# 1_Power.net
KiCad netlist of a schematic drawn in Altium Designer
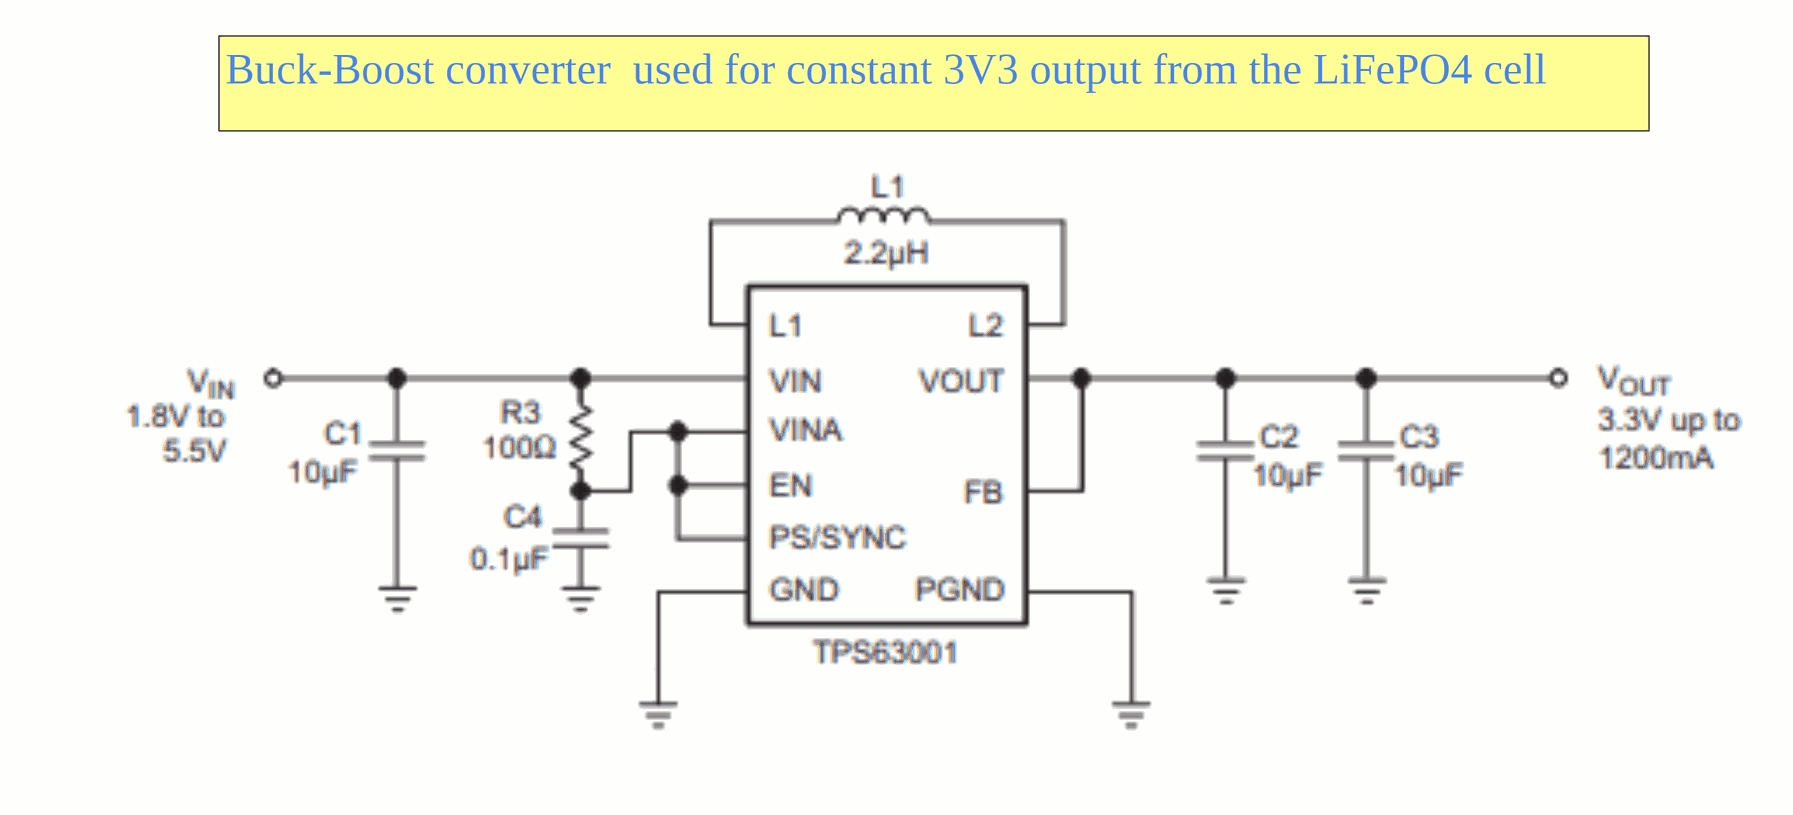
[diagram p0: 1_Power.SchDoc, top left]
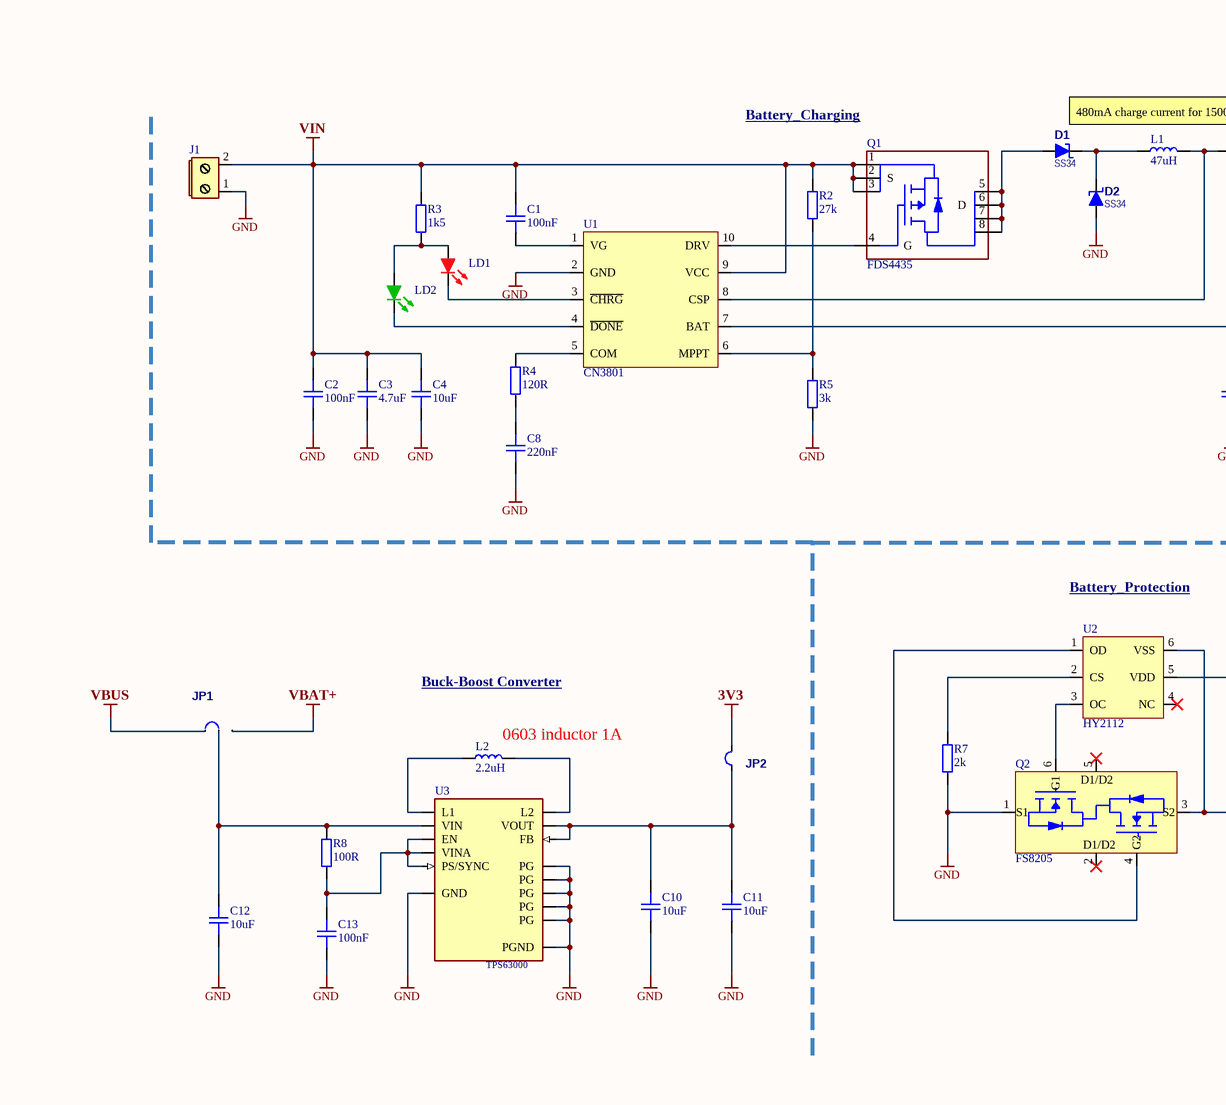
[diagram p1: 1_Power.SchDoc, top middle]
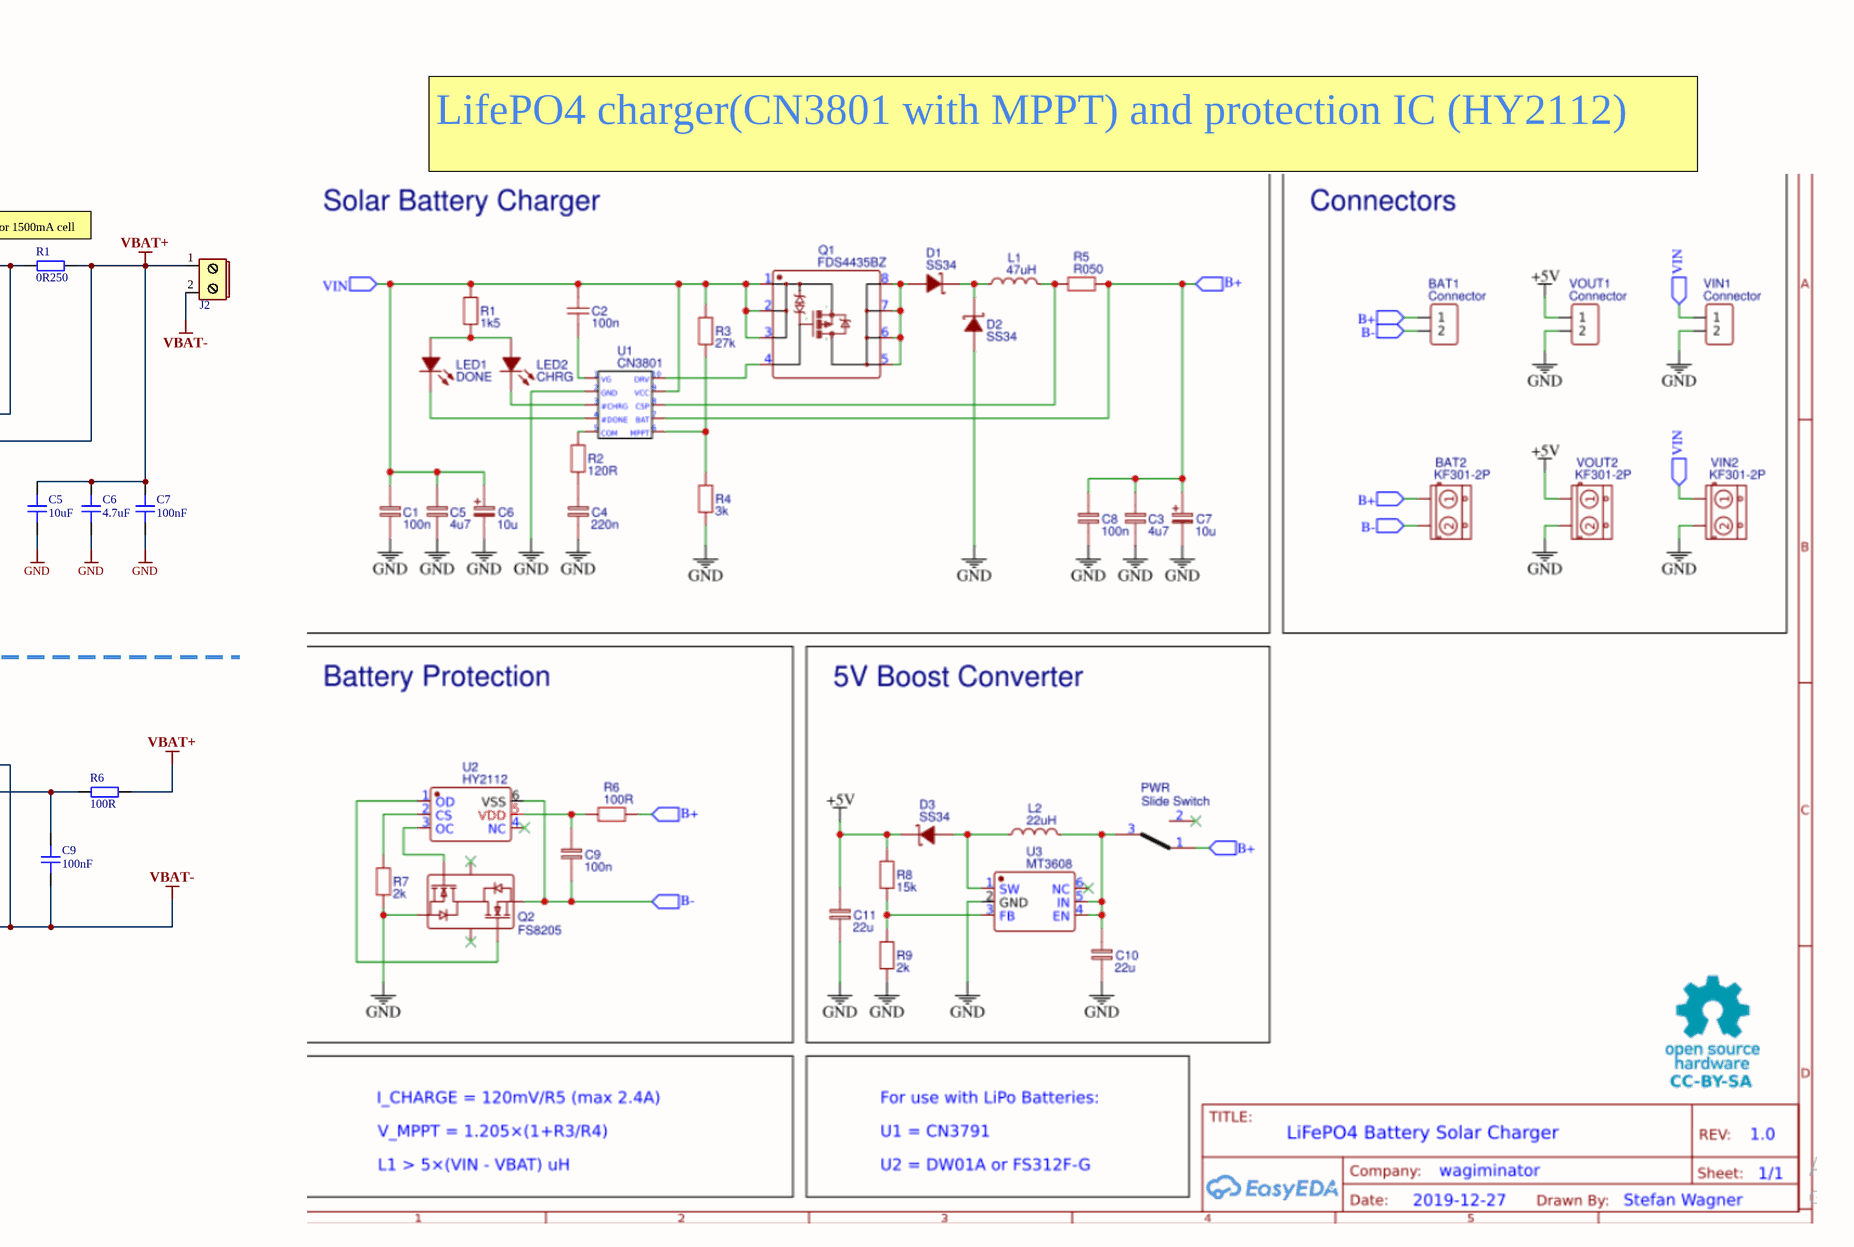
[diagram p2: 1_Power.SchDoc, top right]
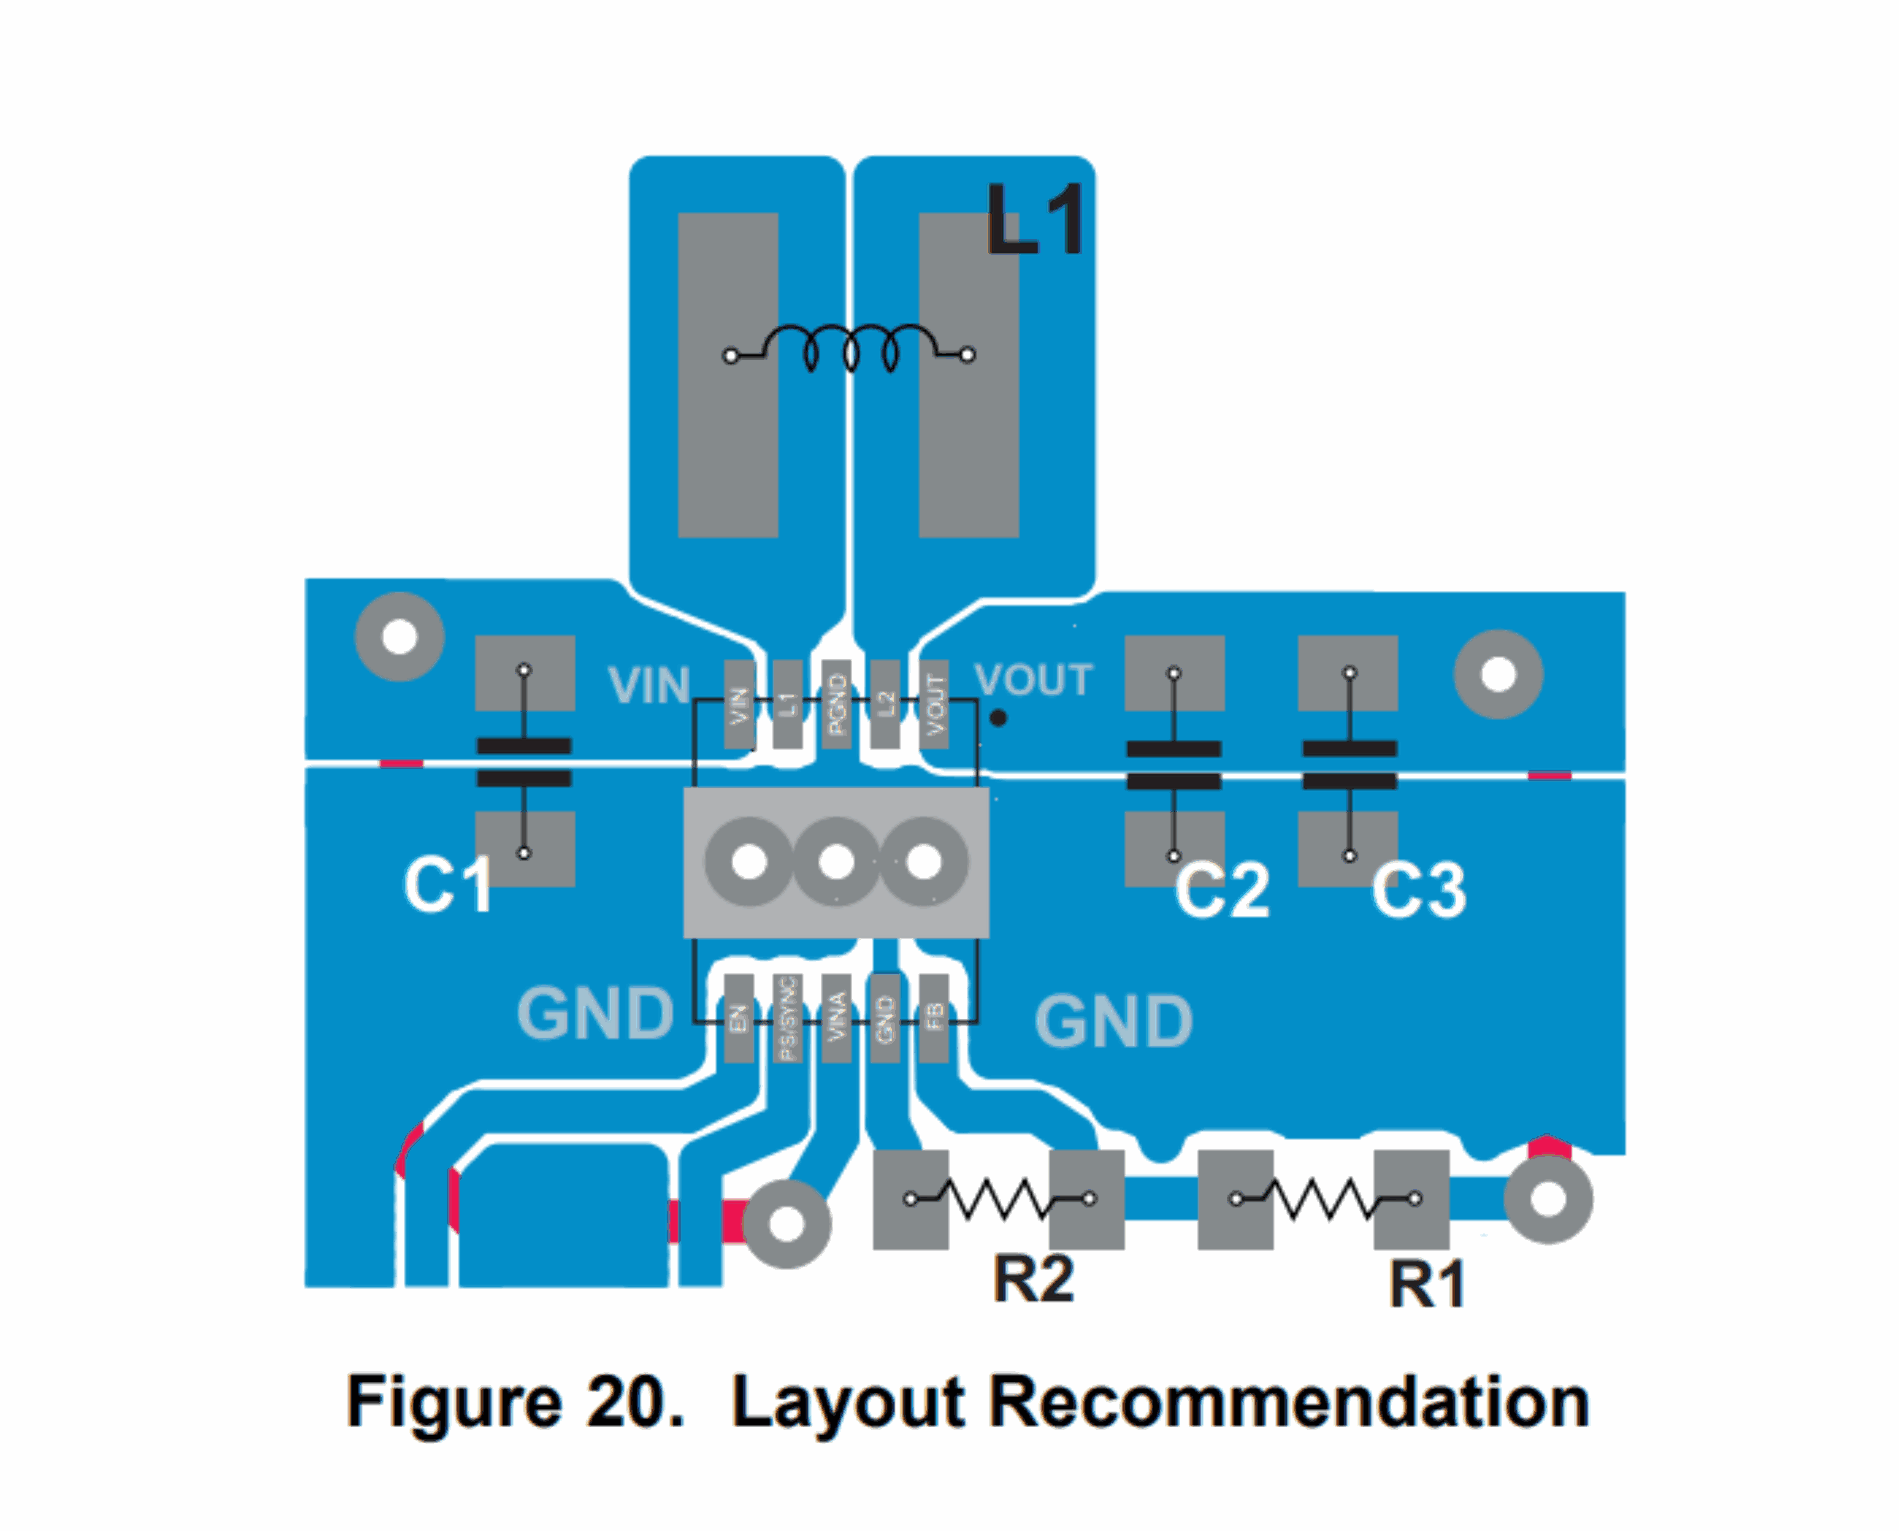
[diagram p3: 1_Power.SchDoc, bottom left]

(export (version "E")
  (design (tool "Eeschema 10.0.6"))
  (components
    (comp (ref "C1")
      (value "100nF")
      (footprint "C0603")
      (description "Capacitor SMD 0603")
      (libsource (lib "Schlib1") (part "CAP_0603"))
    )
    (comp (ref "C2")
      (value "100nF")
      (footprint "C0603")
      (description "Capacitor SMD 0603")
      (libsource (lib "Schlib1") (part "CAP_0603"))
    )
    (comp (ref "C3")
      (value "4.7uF")
      (footprint "C0603")
      (description "Capacitor SMD 0603")
      (libsource (lib "Schlib1") (part "CAP_0603"))
    )
    (comp (ref "C4")
      (value "10uF")
      (footprint "C0805")
      (description "Capacitor SMD 0805")
      (libsource (lib "Schlib1") (part "CAP_0805"))
    )
    (comp (ref "C5")
      (value "10uF")
      (footprint "C0805")
      (description "Capacitor SMD 0805")
      (libsource (lib "Schlib1") (part "CAP_0805"))
    )
    (comp (ref "C6")
      (value "4.7uF")
      (footprint "C0603")
      (description "Capacitor SMD 0603")
      (libsource (lib "Schlib1") (part "CAP_0603"))
    )
    (comp (ref "C7")
      (value "100nF")
      (footprint "C0603")
      (description "Capacitor SMD 0603")
      (libsource (lib "Schlib1") (part "CAP_0603"))
    )
    (comp (ref "C8")
      (value "220nF")
      (footprint "C0603")
      (description "Capacitor SMD 0603")
      (libsource (lib "Schlib1") (part "CAP_0603"))
    )
    (comp (ref "C9")
      (value "100nF")
      (footprint "C0603")
      (description "Capacitor SMD 0603")
      (libsource (lib "Schlib1") (part "CAP_0603"))
    )
    (comp (ref "C10")
      (value "10uF")
      (footprint "C0805")
      (description "Capacitor SMD 0805")
      (libsource (lib "Schlib1") (part "CAP_0805"))
    )
    (comp (ref "C11")
      (value "10uF")
      (footprint "C0805")
      (description "Capacitor SMD 0805")
      (libsource (lib "Schlib1") (part "CAP_0805"))
    )
    (comp (ref "C12")
      (value "10uF")
      (footprint "C0805")
      (description "Capacitor SMD 0805")
      (libsource (lib "Schlib1") (part "CAP_0805"))
    )
    (comp (ref "C13")
      (value "100nF")
      (footprint "C0603")
      (description "Capacitor SMD 0603")
      (libsource (lib "Schlib1") (part "CAP_0603"))
    )
    (comp (ref "D1")
      (value "SS34")
      (footprint "DO-214AC")
      (description "Diode")
      (libsource (lib "Schlib1") (part "DIODE_SCHOTTKY"))
    )
    (comp (ref "D2")
      (value "SS34")
      (footprint "DO-214AC")
      (description "Diode")
      (libsource (lib "Schlib1") (part "DIODE_SCHOTTKY"))
    )
    (comp (ref "J1")
      (value "PLUGIN_TERMINAL")
      (footprint "2.54_pluggable_terminal")
      (description "Screw terminal or plug terminal for power")
      (libsource (lib "") (part "Power_Connector_1"))
    )
    (comp (ref "J2")
      (value "PLUGIN_TERMINAL")
      (footprint "HEADER_1x2_2.54")
      (description "Screw terminal or plug terminal for power")
      (libsource (lib "Schlib1") (part "Power_Connector"))
    )
    (comp (ref "JP1")
      (value "JUMPER_3PIN")
      (footprint "HEADER_1x3_2.54")
      (libsource (lib "Schlib1") (part "JUMPER_3PIN"))
    )
    (comp (ref "JP2")
      (value "JUMPER")
      (footprint "HEADER_1x2_2.54")
      (libsource (lib "Schlib1") (part "JUMPER"))
    )
    (comp (ref "L1")
      (value "47uH")
      (footprint "IND_5_7")
      (description "Inductor SMD 0603")
      (libsource (lib "Schlib1") (part "IND_0603"))
    )
    (comp (ref "L2")
      (value "2.2uH")
      (footprint "L0603")
      (description "Inductor SMD 1008")
      (libsource (lib "Schlib1") (part "IND_1008"))
    )
    (comp (ref "LD1")
      (value "LED_RED")
      (footprint "LED0603RD")
      (description "Typical BLUE SiC LED")
      (fields (field (name "PUBLISHER") "Altium Limited"))
      (libsource (lib "Schlib1") (part "LED_RED"))
    )
    (comp (ref "LD2")
      (value "LED_GREEN")
      (footprint "LED0603GR")
      (description "Typical BLUE SiC LED")
      (fields (field (name "PUBLISHER") "Altium Limited"))
      (libsource (lib "Schlib1") (part "LED_GREEN"))
    )
    (comp (ref "Q1") (value "FDS4435") (footprint "SOIC-SN8_N") (libsource (lib "Schlib1") (part "FDS4435")))
    (comp (ref "Q2") (value "FS8205") (footprint "SOT23-6") (libsource (lib "Schlib1") (part "FS8205")))
    (comp (ref "R1")
      (value "0R250")
      (footprint "R2512")
      (description "Resistor SMD 0805")
      (libsource (lib "Schlib1") (part "RES_0805"))
    )
    (comp (ref "R2")
      (value "27k")
      (footprint "R0603")
      (description "Resistor SMD 0603")
      (libsource (lib "Schlib1") (part "RES_0603"))
    )
    (comp (ref "R3")
      (value "1k5")
      (footprint "R0603")
      (description "Resistor SMD 0603")
      (libsource (lib "Schlib1") (part "RES_0603"))
    )
    (comp (ref "R4")
      (value "120R")
      (footprint "R0603")
      (description "Resistor SMD 0603")
      (libsource (lib "Schlib1") (part "RES_0603"))
    )
    (comp (ref "R5")
      (value "3k")
      (footprint "R0603")
      (description "Resistor SMD 0603")
      (libsource (lib "Schlib1") (part "RES_0603"))
    )
    (comp (ref "R6")
      (value "100R")
      (footprint "R0603")
      (description "Resistor SMD 0603")
      (libsource (lib "Schlib1") (part "RES_0603"))
    )
    (comp (ref "R7")
      (value "2k")
      (footprint "R0603")
      (description "Resistor SMD 0603")
      (libsource (lib "Schlib1") (part "RES_0603_1"))
    )
    (comp (ref "R8")
      (value "100R")
      (footprint "R0603")
      (description "Resistor SMD 0603")
      (libsource (lib "Schlib1") (part "RES_0603"))
    )
    (comp (ref "U1") (value "CN3801") (footprint "SSOP-10") (libsource (lib "Schlib1") (part "CN3801")))
    (comp (ref "U2")
      (value "HY2112")
      (footprint "SOT23-6")
      (description "LiFePO4 protection IC")
      (libsource (lib "Schlib1") (part "HY2112"))
    )
    (comp (ref "U3")
      (value "TPS63001")
      (footprint "VREG_V62/16624-01YE")
      (fields (field (name "MP") "TPS63000") (field (name "MF") "Texas Instruments"))
      (libsource (lib "Schlib1") (part "TPS63000"))
    )
  )
  (nets
    (net (code "1") (name "3V3") (class "Default")
      (node (ref "JP2") (pin "2") (pinfunction "2_2") (pintype "passive"))
    )
    (net (code "2") (name "GND") (class "Default")
      (node (ref "C10") (pin "1") (pinfunction "1_1") (pintype "passive"))
      (node (ref "C11") (pin "1") (pinfunction "1_1") (pintype "passive"))
      (node (ref "C12") (pin "1") (pinfunction "1_1") (pintype "passive"))
      (node (ref "C13") (pin "1") (pinfunction "1_1") (pintype "passive"))
      (node (ref "C2") (pin "1") (pinfunction "1_1") (pintype "passive"))
      (node (ref "C3") (pin "1") (pinfunction "1_1") (pintype "passive"))
      (node (ref "C4") (pin "1") (pinfunction "1_1") (pintype "passive"))
      (node (ref "C5") (pin "1") (pinfunction "1_1") (pintype "passive"))
      (node (ref "C6") (pin "1") (pinfunction "1_1") (pintype "passive"))
      (node (ref "C7") (pin "1") (pinfunction "1_1") (pintype "passive"))
      (node (ref "C8") (pin "1") (pinfunction "1_1") (pintype "passive"))
      (node (ref "D2") (pin "1") (pinfunction "A_1") (pintype "passive"))
      (node (ref "J1") (pin "1") (pinfunction "1_1") (pintype "passive"))
      (node (ref "Q2") (pin "1") (pinfunction "S1_1") (pintype "passive"))
      (node (ref "R5") (pin "1") (pinfunction "1_1") (pintype "passive"))
      (node (ref "R7") (pin "1") (pinfunction "1_1") (pintype "passive"))
      (node (ref "U1") (pin "2") (pinfunction "GND_2") (pintype "passive"))
      (node (ref "U3") (pin "11") (pinfunction "PG_11") (pintype "power_in"))
      (node (ref "U3") (pin "3") (pinfunction "PGND_3") (pintype "power_in"))
      (node (ref "U3") (pin "9") (pinfunction "GND_9") (pintype "power_in"))
    )
    (net (code "3") (name "Net-(C8-Pad2)") (class "Default")
      (node (ref "C8") (pin "2") (pinfunction "2_2") (pintype "passive"))
      (node (ref "R4") (pin "1") (pinfunction "1_1") (pintype "passive"))
    )
    (net (code "4") (name "Net-(D1-A)") (class "Default")
      (node (ref "D1") (pin "1") (pinfunction "A_1") (pintype "passive"))
      (node (ref "Q1") (pin "5") (pinfunction "D_5") (pintype "passive"))
      (node (ref "Q1") (pin "6") (pinfunction "D_6") (pintype "passive"))
      (node (ref "Q1") (pin "7") (pinfunction "D_7") (pintype "passive"))
      (node (ref "Q1") (pin "8") (pinfunction "D_8") (pintype "passive"))
    )
    (net (code "5") (name "Net-(D1-K)") (class "Default")
      (node (ref "D1") (pin "2") (pinfunction "K_2") (pintype "passive"))
      (node (ref "D2") (pin "2") (pinfunction "K_2") (pintype "passive"))
      (node (ref "L1") (pin "1") (pinfunction "1_1") (pintype "passive"))
    )
    (net (code "6") (name "Net-(LD1-A)") (class "Default")
      (node (ref "LD1") (pin "1") (pinfunction "A_1") (pintype "passive"))
      (node (ref "LD2") (pin "1") (pinfunction "A_1") (pintype "passive"))
      (node (ref "R3") (pin "1") (pinfunction "1_1") (pintype "passive"))
    )
    (net (code "7") (name "Net-(LD1-K)") (class "Default")
      (node (ref "LD1") (pin "2") (pinfunction "K_2") (pintype "passive"))
      (node (ref "U1") (pin "3") (pinfunction "CHRG_3") (pintype "passive"))
    )
    (net (code "8") (name "Net-(LD2-K)") (class "Default")
      (node (ref "LD2") (pin "2") (pinfunction "K_2") (pintype "passive"))
      (node (ref "U1") (pin "4") (pinfunction "DONE_4") (pintype "passive"))
    )
    (net (code "9") (name "Net-(Q1-G)") (class "Default")
      (node (ref "Q1") (pin "4") (pinfunction "G_4") (pintype "passive"))
      (node (ref "U1") (pin "10") (pinfunction "DRV_10") (pintype "passive"))
    )
    (net (code "10") (name "Net-(Q2-G1)") (class "Default")
      (node (ref "Q2") (pin "6") (pinfunction "G1_6") (pintype "passive"))
      (node (ref "U2") (pin "3") (pinfunction "OC_3") (pintype "passive"))
    )
    (net (code "11") (name "Net-(Q2-G2)") (class "Default")
      (node (ref "Q2") (pin "4") (pinfunction "G2_4") (pintype "passive"))
      (node (ref "U2") (pin "1") (pinfunction "OD_1") (pintype "passive"))
    )
    (net (code "12") (name "Net-(U1-COM)") (class "Default")
      (node (ref "R4") (pin "2") (pinfunction "2_2") (pintype "passive"))
      (node (ref "U1") (pin "5") (pinfunction "COM_5") (pintype "passive"))
    )
    (net (code "13") (name "Net-(U1-CSP)") (class "Default")
      (node (ref "L1") (pin "2") (pinfunction "2_2") (pintype "passive"))
      (node (ref "R1") (pin "1") (pinfunction "1_1") (pintype "passive"))
      (node (ref "U1") (pin "8") (pinfunction "CSP_8") (pintype "passive"))
    )
    (net (code "14") (name "Net-(U1-MPPT)") (class "Default")
      (node (ref "R2") (pin "1") (pinfunction "1_1") (pintype "passive"))
      (node (ref "R5") (pin "2") (pinfunction "2_2") (pintype "passive"))
      (node (ref "U1") (pin "6") (pinfunction "MPPT_6") (pintype "passive"))
    )
    (net (code "15") (name "Net-(U1-VG)") (class "Default")
      (node (ref "C1") (pin "1") (pinfunction "1_1") (pintype "passive"))
      (node (ref "U1") (pin "1") (pinfunction "VG_1") (pintype "passive"))
    )
    (net (code "16") (name "Net-(U2-CS)") (class "Default")
      (node (ref "R7") (pin "2") (pinfunction "2_2") (pintype "passive"))
      (node (ref "U2") (pin "2") (pinfunction "CS_2") (pintype "passive"))
    )
    (net (code "17") (name "Net-(U2-VDD)") (class "Default")
      (node (ref "C9") (pin "2") (pinfunction "2_2") (pintype "passive"))
      (node (ref "R6") (pin "2") (pinfunction "2_2") (pintype "passive"))
      (node (ref "U2") (pin "5") (pinfunction "VDD_5") (pintype "passive"))
    )
    (net (code "18") (name "Net-(U3-EN)") (class "Default")
      (node (ref "C13") (pin "2") (pinfunction "2_2") (pintype "passive"))
      (node (ref "R8") (pin "1") (pinfunction "1_1") (pintype "passive"))
      (node (ref "U3") (pin "6") (pinfunction "EN_6") (pintype "bidirectional"))
      (node (ref "U3") (pin "7") (pinfunction "PS/SYNC_7") (pintype "input"))
      (node (ref "U3") (pin "8") (pinfunction "VINA_8") (pintype "power_in"))
    )
    (net (code "19") (name "Net-(U3-FB)") (class "Default")
      (node (ref "C10") (pin "2") (pinfunction "2_2") (pintype "passive"))
      (node (ref "C11") (pin "2") (pinfunction "2_2") (pintype "passive"))
      (node (ref "JP2") (pin "1") (pinfunction "1_1") (pintype "passive"))
      (node (ref "U3") (pin "1") (pinfunction "VOUT_1") (pintype "power_in"))
      (node (ref "U3") (pin "10") (pinfunction "FB_10") (pintype "input"))
    )
    (net (code "20") (name "Net-(U3-L1)") (class "Default")
      (node (ref "L2") (pin "1") (pinfunction "1_1") (pintype "passive"))
      (node (ref "U3") (pin "4") (pinfunction "L1_4") (pintype "passive"))
    )
    (net (code "21") (name "Net-(U3-L2)") (class "Default")
      (node (ref "L2") (pin "2") (pinfunction "2_2") (pintype "passive"))
      (node (ref "U3") (pin "2") (pinfunction "L2_2") (pintype "passive"))
    )
    (net (code "22") (name "Net-(U3-VIN)") (class "Default")
      (node (ref "C12") (pin "2") (pinfunction "2_2") (pintype "passive"))
      (node (ref "JP1") (pin "2") (pinfunction "2_2") (pintype "passive"))
      (node (ref "R8") (pin "2") (pinfunction "2_2") (pintype "passive"))
      (node (ref "U3") (pin "5") (pinfunction "VIN_5") (pintype "power_in"))
    )
    (net (code "23") (name "VBAT+") (class "Default")
      (node (ref "C5") (pin "2") (pinfunction "2_2") (pintype "passive"))
      (node (ref "C6") (pin "2") (pinfunction "2_2") (pintype "passive"))
      (node (ref "C7") (pin "2") (pinfunction "2_2") (pintype "passive"))
      (node (ref "J2") (pin "1") (pinfunction "1_1") (pintype "passive"))
      (node (ref "JP1") (pin "3") (pinfunction "3_3") (pintype "passive"))
      (node (ref "R1") (pin "2") (pinfunction "2_2") (pintype "passive"))
      (node (ref "R6") (pin "1") (pinfunction "1_1") (pintype "passive"))
      (node (ref "U1") (pin "7") (pinfunction "BAT_7") (pintype "passive"))
    )
    (net (code "24") (name "VBAT-") (class "Default")
      (node (ref "C9") (pin "1") (pinfunction "1_1") (pintype "passive"))
      (node (ref "J2") (pin "2") (pinfunction "2_2") (pintype "passive"))
      (node (ref "Q2") (pin "3") (pinfunction "S2_3") (pintype "passive"))
      (node (ref "U2") (pin "6") (pinfunction "VSS_6") (pintype "passive"))
    )
    (net (code "25") (name "VBUS") (class "Default")
      (node (ref "JP1") (pin "1") (pinfunction "1_1") (pintype "passive"))
    )
    (net (code "26") (name "VIN") (class "Default")
      (node (ref "C1") (pin "2") (pinfunction "2_2") (pintype "passive"))
      (node (ref "C2") (pin "2") (pinfunction "2_2") (pintype "passive"))
      (node (ref "C3") (pin "2") (pinfunction "2_2") (pintype "passive"))
      (node (ref "C4") (pin "2") (pinfunction "2_2") (pintype "passive"))
      (node (ref "J1") (pin "2") (pinfunction "2_2") (pintype "passive"))
      (node (ref "Q1") (pin "1") (pinfunction "S_1") (pintype "passive"))
      (node (ref "Q1") (pin "2") (pinfunction "S_2") (pintype "passive"))
      (node (ref "Q1") (pin "3") (pinfunction "S_3") (pintype "passive"))
      (node (ref "R2") (pin "2") (pinfunction "2_2") (pintype "passive"))
      (node (ref "R3") (pin "2") (pinfunction "2_2") (pintype "passive"))
      (node (ref "U1") (pin "9") (pinfunction "VCC_9") (pintype "passive"))
    )
    (net (code "27") (name "unconnected-(Q2-D1{slash}D2-Pad2)") (class "Default")
      (node (ref "Q2") (pin "2") (pinfunction "D1/D2_2") (pintype "passive+no_connect"))
    )
    (net (code "28") (name "unconnected-(Q2-D1{slash}D2-Pad5)") (class "Default")
      (node (ref "Q2") (pin "5") (pinfunction "D1/D2_5") (pintype "passive+no_connect"))
    )
    (net (code "29") (name "unconnected-(U2-NC-Pad4)") (class "Default")
      (node (ref "U2") (pin "4") (pinfunction "NC_4") (pintype "passive+no_connect"))
    )
  )
)
